# Schematic_-_Ebook_Reader_vFinal_v34.net
KiCad netlist of a schematic drawn in EAGLE
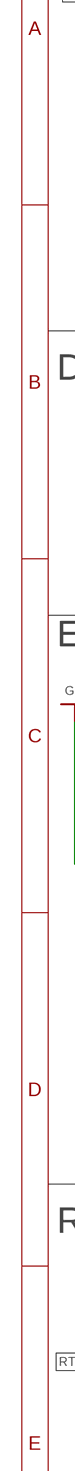
[diagram p0: schematic, sheet 1, part 1 of 2]
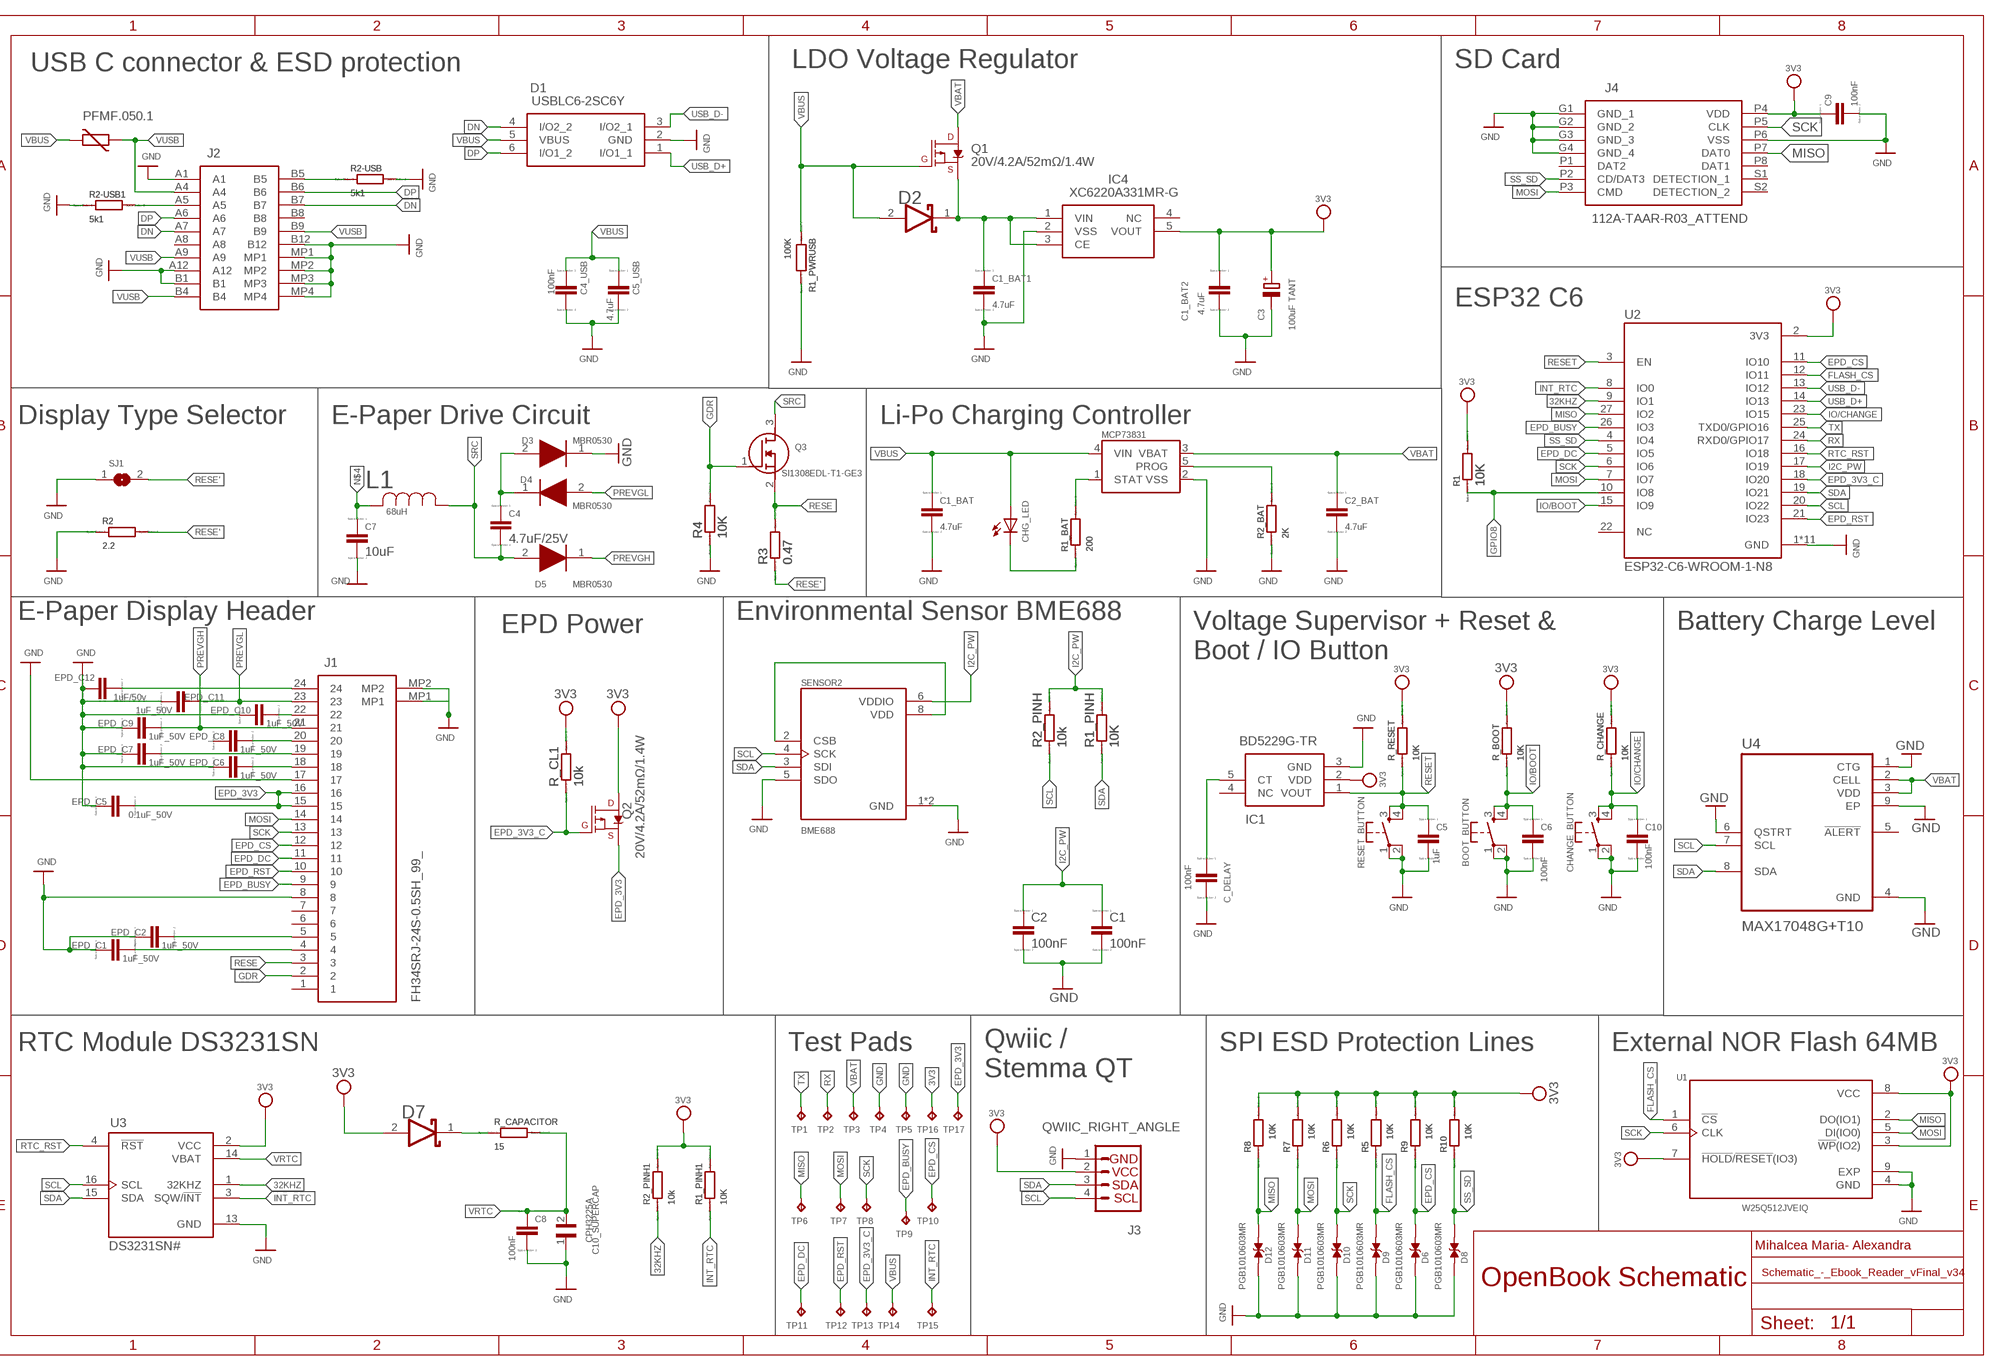
[diagram p1: schematic, sheet 1, part 2 of 2]

(export (version "E")
  (design (tool "Eeschema 10.0.6"))
  (components
    (comp (ref "BOOT_BUTTON")
      (value "BUTTON_CUSYOMV1")
      (footprint "eagle-import:MYBUTTON")
      (libsource (lib "eagle-import") (part "BUTTON_CUSYOMV1"))
    )
    (comp (ref "C1")
      (value "100nF")
      (footprint "eagle-import:EAGLE-LTSPICE_C0402")
      (libsource (lib "eagle-import") (part "EAGLE-LTSPICE_CC0402"))
    )
    (comp (ref "C1_BAT")
      (value "4.7uF")
      (footprint "eagle-import:EAGLE-LTSPICE_C0402")
      (libsource (lib "eagle-import") (part "EAGLE-LTSPICE_CC0402"))
    )
    (comp (ref "C1_BAT1")
      (value "4.7uF")
      (footprint "eagle-import:EAGLE-LTSPICE_C0402")
      (libsource (lib "eagle-import") (part "EAGLE-LTSPICE_CC0402"))
    )
    (comp (ref "C1_BAT2")
      (value "4.7uF")
      (footprint "eagle-import:EAGLE-LTSPICE_C0402")
      (libsource (lib "eagle-import") (part "EAGLE-LTSPICE_CC0402"))
    )
    (comp (ref "C2")
      (value "100nF")
      (footprint "eagle-import:EAGLE-LTSPICE_C0402")
      (libsource (lib "eagle-import") (part "EAGLE-LTSPICE_CC0402"))
    )
    (comp (ref "C2_BAT")
      (value "4.7uF")
      (footprint "eagle-import:EAGLE-LTSPICE_C0402")
      (libsource (lib "eagle-import") (part "EAGLE-LTSPICE_CC0402"))
    )
    (comp (ref "C3")
      (value "100uF TANT")
      (footprint "eagle-import:RCL_CT3528")
      (libsource (lib "eagle-import") (part "RCL_CPOL-EUCT3528"))
    )
    (comp (ref "C4")
      (value "4.7uF/25V")
      (footprint "eagle-import:EAGLE-LTSPICE_C0402")
      (libsource (lib "eagle-import") (part "EAGLE-LTSPICE_CC0402"))
    )
    (comp (ref "C4_USB")
      (value "100nF")
      (footprint "eagle-import:EAGLE-LTSPICE_C0402")
      (libsource (lib "eagle-import") (part "EAGLE-LTSPICE_CC0402"))
    )
    (comp (ref "C5")
      (value "1uF")
      (footprint "eagle-import:EAGLE-LTSPICE_C0402")
      (libsource (lib "eagle-import") (part "EAGLE-LTSPICE_CC0402"))
    )
    (comp (ref "C5_USB")
      (value "4.7uF")
      (footprint "eagle-import:EAGLE-LTSPICE_C0402")
      (libsource (lib "eagle-import") (part "EAGLE-LTSPICE_CC0402"))
    )
    (comp (ref "C6")
      (value "100nF")
      (footprint "eagle-import:EAGLE-LTSPICE_C0402")
      (libsource (lib "eagle-import") (part "EAGLE-LTSPICE_CC0402"))
    )
    (comp (ref "C7")
      (value "10uF")
      (footprint "eagle-import:EAGLE-LTSPICE_C0402")
      (libsource (lib "eagle-import") (part "EAGLE-LTSPICE_CC0402"))
    )
    (comp (ref "C8")
      (value "100nF")
      (footprint "eagle-import:EAGLE-LTSPICE_C0402")
      (libsource (lib "eagle-import") (part "EAGLE-LTSPICE_CC0402"))
    )
    (comp (ref "C9")
      (value "100nF")
      (footprint "eagle-import:EAGLE-LTSPICE_C0402")
      (libsource (lib "eagle-import") (part "EAGLE-LTSPICE_CC0402"))
    )
    (comp (ref "C10")
      (value "100nF")
      (footprint "eagle-import:EAGLE-LTSPICE_C0402")
      (libsource (lib "eagle-import") (part "EAGLE-LTSPICE_CC0402"))
    )
    (comp (ref "C10_SUPERCAP")
      (value "CPH3225A")
      (footprint "eagle-import:CAPCP3225X100N")
      (fields (field (name "MF") "Seiko Instruments"))
      (libsource (lib "eagle-import") (part "CPH3225A"))
    )
    (comp (ref "CHANGE_BUTTON")
      (value "BUTTON_CUSYOMV1")
      (footprint "eagle-import:MYBUTTON")
      (libsource (lib "eagle-import") (part "BUTTON_CUSYOMV1"))
    )
    (comp (ref "CHG_LED")
      (value "ADAFRUIT_LEDCHIP-LED0603")
      (footprint "eagle-import:ADAFRUIT_CHIP-LED0603")
      (libsource (lib "eagle-import") (part "ADAFRUIT_LEDCHIP-LED0603"))
    )
    (comp (ref "C_DELAY")
      (value "100nF")
      (footprint "eagle-import:EAGLE-LTSPICE_C0402")
      (libsource (lib "eagle-import") (part "EAGLE-LTSPICE_CC0402"))
    )
    (comp (ref "D1")
      (value "USBLC6-2SC6Y")
      (footprint "eagle-import:SOT95P280X145-6N")
      (fields (field (name "MF") "STMicroelectronics"))
      (libsource (lib "eagle-import") (part "USBLC6-2SC6Y"))
    )
    (comp (ref "D2")
      (value "ESP32_WROVER_AVX---SD0805S020S1R0_AVX_SD0805S020S1R0_0_0AVX_SD0805S020S1R0_0_0")
      (footprint "eagle-import:ESP32_WROVER_AVX---SD0805S020S1R0_AVX_SD0805S020S1R0_0")
      (fields
        (field (name "DIGIKEY_PART_NUMBER") "478-7800-1-ND")
        (field (name "MF") "AVX")
        (field (name "MOUSER_PART_NUMBER") "581-SD0805S020S1R0")
      )
      (libsource (lib "eagle-import") (part "ESP32_WROVER_AVX---SD0805S020S1R0_AVX_SD0805S020S1R0_0_0AVX_SD0805S020S1R0_0_0"))
    )
    (comp (ref "D3")
      (value "MBR0530")
      (footprint "eagle-import:SOD3716X135N")
      (fields (field (name "MF") "ON Semiconductor"))
      (libsource (lib "eagle-import") (part "MBR0530"))
    )
    (comp (ref "D4")
      (value "MBR0530")
      (footprint "eagle-import:SOD3716X135N")
      (fields (field (name "MF") "ON Semiconductor"))
      (libsource (lib "eagle-import") (part "MBR0530"))
    )
    (comp (ref "D5")
      (value "MBR0530")
      (footprint "eagle-import:SOD3716X135N")
      (fields (field (name "MF") "ON Semiconductor"))
      (libsource (lib "eagle-import") (part "MBR0530"))
    )
    (comp (ref "D6")
      (value "PGB1010603MR")
      (footprint "eagle-import:DIOC1608X36N")
      (fields (field (name "MF") "Littelfuse Inc."))
      (libsource (lib "eagle-import") (part "PGB1010603MR"))
    )
    (comp (ref "D7")
      (value "ESP32_WROVER_AVX---SD0805S020S1R0_AVX_SD0805S020S1R0_0_0AVX_SD0805S020S1R0_0_0")
      (footprint "eagle-import:ESP32_WROVER_AVX---SD0805S020S1R0_AVX_SD0805S020S1R0_0")
      (fields
        (field (name "DIGIKEY_PART_NUMBER") "478-7800-1-ND")
        (field (name "MF") "AVX")
        (field (name "MOUSER_PART_NUMBER") "581-SD0805S020S1R0")
      )
      (libsource (lib "eagle-import") (part "ESP32_WROVER_AVX---SD0805S020S1R0_AVX_SD0805S020S1R0_0_0AVX_SD0805S020S1R0_0_0"))
    )
    (comp (ref "D8")
      (value "PGB1010603MR")
      (footprint "eagle-import:DIOC1608X36N")
      (fields (field (name "MF") "Littelfuse Inc."))
      (libsource (lib "eagle-import") (part "PGB1010603MR"))
    )
    (comp (ref "D9")
      (value "PGB1010603MR")
      (footprint "eagle-import:DIOC1608X36N")
      (fields (field (name "MF") "Littelfuse Inc."))
      (libsource (lib "eagle-import") (part "PGB1010603MR"))
    )
    (comp (ref "D10")
      (value "PGB1010603MR")
      (footprint "eagle-import:DIOC1608X36N")
      (fields (field (name "MF") "Littelfuse Inc."))
      (libsource (lib "eagle-import") (part "PGB1010603MR"))
    )
    (comp (ref "D11")
      (value "PGB1010603MR")
      (footprint "eagle-import:DIOC1608X36N")
      (fields (field (name "MF") "Littelfuse Inc."))
      (libsource (lib "eagle-import") (part "PGB1010603MR"))
    )
    (comp (ref "D12")
      (value "PGB1010603MR")
      (footprint "eagle-import:DIOC1608X36N")
      (fields (field (name "MF") "Littelfuse Inc."))
      (libsource (lib "eagle-import") (part "PGB1010603MR"))
    )
    (comp (ref "EPD_C1")
      (value "1uF_50V")
      (footprint "eagle-import:EAGLE-LTSPICE_C0402")
      (libsource (lib "eagle-import") (part "EAGLE-LTSPICE_CC0402"))
    )
    (comp (ref "EPD_C2")
      (value "1uF_50V")
      (footprint "eagle-import:EAGLE-LTSPICE_C0402")
      (libsource (lib "eagle-import") (part "EAGLE-LTSPICE_CC0402"))
    )
    (comp (ref "EPD_C5")
      (value "0.1uF_50V")
      (footprint "eagle-import:EAGLE-LTSPICE_C0402")
      (libsource (lib "eagle-import") (part "EAGLE-LTSPICE_CC0402"))
    )
    (comp (ref "EPD_C6")
      (value "1uF_50V")
      (footprint "eagle-import:EAGLE-LTSPICE_C0402")
      (libsource (lib "eagle-import") (part "EAGLE-LTSPICE_CC0402"))
    )
    (comp (ref "EPD_C7")
      (value "1uF_50V")
      (footprint "eagle-import:EAGLE-LTSPICE_C0402")
      (libsource (lib "eagle-import") (part "EAGLE-LTSPICE_CC0402"))
    )
    (comp (ref "EPD_C8")
      (value "1uF_50V")
      (footprint "eagle-import:EAGLE-LTSPICE_C0402")
      (libsource (lib "eagle-import") (part "EAGLE-LTSPICE_CC0402"))
    )
    (comp (ref "EPD_C9")
      (value "1uF_50V")
      (footprint "eagle-import:EAGLE-LTSPICE_C0402")
      (libsource (lib "eagle-import") (part "EAGLE-LTSPICE_CC0402"))
    )
    (comp (ref "EPD_C10")
      (value "1uF_50V")
      (footprint "eagle-import:EAGLE-LTSPICE_C0402")
      (libsource (lib "eagle-import") (part "EAGLE-LTSPICE_CC0402"))
    )
    (comp (ref "EPD_C11")
      (value "1uF_50V")
      (footprint "eagle-import:EAGLE-LTSPICE_C0402")
      (libsource (lib "eagle-import") (part "EAGLE-LTSPICE_CC0402"))
    )
    (comp (ref "EPD_C12")
      (value "1uF/50v")
      (footprint "eagle-import:EAGLE-LTSPICE_C0402")
      (libsource (lib "eagle-import") (part "EAGLE-LTSPICE_CC0402"))
    )
    (comp (ref "IC1")
      (value "BD5229G-TR")
      (footprint "eagle-import:SOT95P280X125-5N")
      (fields (field (name "MOUSER_PART_NUMBER") "755-BD5229G-TR"))
      (libsource (lib "eagle-import") (part "BD5229G-TR"))
    )
    (comp (ref "IC4")
      (value "XC6220A331MR-G")
      (footprint "eagle-import:SOT95P280X120-5N")
      (fields (field (name "MOUSER_PART_NUMBER") "865-XC6220A331MR-G"))
      (libsource (lib "eagle-import") (part "XC6220A331MR-G"))
    )
    (comp (ref "J1")
      (value "FH34SRJ-24S-0.5SH_99_")
      (footprint "eagle-import:FH34SRJ24S05SH99")
      (fields
        (field (name "MANUFACTURER_PART_NUMBER") "FH34SRJ-24S-0.5SH(99)")
        (field (name "MOUSER_PART_NUMBER") "798-FH34SRJ24S05SH99")
      )
      (libsource (lib "eagle-import") (part "FH34SRJ-24S-0.5SH_99_"))
    )
    (comp (ref "J2")
      (value "SAMACSYS_PARTS_USB4110-GF-A")
      (footprint "eagle-import:SAMACSYS_PARTS_USB4110GFA")
      (fields
        (field (name "MANUFACTURER_PART_NUMBER") "USB4110-GF-A")
        (field (name "MOUSER_PART_NUMBER") "640-USB4110-GF-A")
      )
      (libsource (lib "eagle-import") (part "SAMACSYS_PARTS_USB4110-GF-A"))
    )
    (comp (ref "J3")
      (value "QWIIC_RIGHT_ANGLE")
      (footprint "eagle-import:JST04_1MM_RA")
      (libsource (lib "eagle-import") (part "QWIIC_CONNECTORJS-1MM"))
    )
    (comp (ref "J4")
      (value "112A-TAAR-R03_ATTEND")
      (footprint "eagle-import:112ATAARR03ATTEND")
      (fields (field (name "MANUFACTURER_PART_NUMBER") "112A-TAAR-R03 ATTEND"))
      (libsource (lib "eagle-import") (part "112A-TAAR-R03_ATTEND"))
    )
    (comp (ref "L1")
      (value "68uH")
      (footprint "eagle-import:IND_4828-WE-TPC_WRE")
      (fields
        (field (name "MANUFACTURER_PART_NUMBER") "744043680")
        (field (name "COPYRIGHT") "Copyright (C) 2024 Ultra Librarian. All rights reserved.")
      )
      (libsource (lib "eagle-import") (part "744043680IND_4828-WE-TPC_WRE"))
    )
    (comp (ref "MCP73831")
      (value "ESP32_WROVER_SPARKFUN-IC-POWER_MCP73831")
      (footprint "eagle-import:ESP32_WROVER_SPARKFUN-IC-POWER_SOT23-5")
      (libsource (lib "eagle-import") (part "ESP32_WROVER_SPARKFUN-IC-POWER_MCP73831"))
    )
    (comp (ref "PFMF.050.1")
      (value "ESP32C6_VARISTORCN1812")
      (footprint "eagle-import:ESP32C6_VARISTOR_CT_CN1812")
      (libsource (lib "eagle-import") (part "ESP32C6_VARISTORCN1812"))
    )
    (comp (ref "Q1")
      (value "20V/4.2A/52mΩ/1.4W")
      (footprint "eagle-import:ESP32_WROVER_SPARKFUN-DISCRETESEMI_SOT23-3")
      (libsource (lib "eagle-import") (part "ESP32_WROVER_SPARKFUN-DISCRETESEMI_MOSFET_PCH-DMG2305UX-7"))
    )
    (comp (ref "Q2")
      (value "20V/4.2A/52mΩ/1.4W")
      (footprint "eagle-import:ESP32_WROVER_SPARKFUN-DISCRETESEMI_SOT23-3")
      (libsource (lib "eagle-import") (part "ESP32_WROVER_SPARKFUN-DISCRETESEMI_MOSFET_PCH-DMG2305UX-7"))
    )
    (comp (ref "Q3")
      (value "SI1308EDL-T1-GE3")
      (footprint "eagle-import:SOT65P210X110-3N")
      (fields (field (name "MF") "Vishay Siliconix"))
      (libsource (lib "eagle-import") (part "SI1308EDL-T1-GE3"))
    )
    (comp (ref "R1")
      (value "10K")
      (footprint "eagle-import:ESP32_WROVER_EAGLE-LTSPICE_R0402")
      (libsource (lib "eagle-import") (part "ESP32_WROVER_EAGLE-LTSPICE_RR0402"))
    )
    (comp (ref "R1_BAT")
      (value "200")
      (footprint "eagle-import:ESP32_WROVER_EAGLE-LTSPICE_R0402")
      (libsource (lib "eagle-import") (part "ESP32_WROVER_EAGLE-LTSPICE_RR0402"))
    )
    (comp (ref "R1_PINH")
      (value "10K")
      (footprint "eagle-import:ESP32_WROVER_EAGLE-LTSPICE_R0402")
      (libsource (lib "eagle-import") (part "ESP32_WROVER_EAGLE-LTSPICE_RR0402"))
    )
    (comp (ref "R1_PINH1")
      (value "10K")
      (footprint "eagle-import:ESP32_WROVER_EAGLE-LTSPICE_R0402")
      (libsource (lib "eagle-import") (part "ESP32_WROVER_EAGLE-LTSPICE_RR0402"))
    )
    (comp (ref "R1_PWRUSB")
      (value "100K")
      (footprint "eagle-import:ESP32_WROVER_EAGLE-LTSPICE_R0402")
      (libsource (lib "eagle-import") (part "ESP32_WROVER_EAGLE-LTSPICE_RR0402"))
    )
    (comp (ref "R2")
      (value "2.2")
      (footprint "eagle-import:ESP32_WROVER_EAGLE-LTSPICE_R0402")
      (libsource (lib "eagle-import") (part "ESP32_WROVER_EAGLE-LTSPICE_RR0402"))
    )
    (comp (ref "R2-USB")
      (value "5k1")
      (footprint "eagle-import:ESP32_WROVER_EAGLE-LTSPICE_R0402")
      (libsource (lib "eagle-import") (part "ESP32_WROVER_EAGLE-LTSPICE_RR0402"))
    )
    (comp (ref "R2-USB1")
      (value "5k1")
      (footprint "eagle-import:ESP32_WROVER_EAGLE-LTSPICE_R0402")
      (libsource (lib "eagle-import") (part "ESP32_WROVER_EAGLE-LTSPICE_RR0402"))
    )
    (comp (ref "R2_BAT")
      (value "2K")
      (footprint "eagle-import:ESP32_WROVER_EAGLE-LTSPICE_R0402")
      (libsource (lib "eagle-import") (part "ESP32_WROVER_EAGLE-LTSPICE_RR0402"))
    )
    (comp (ref "R2_PINH")
      (value "10k")
      (footprint "eagle-import:ESP32_WROVER_EAGLE-LTSPICE_R0402")
      (libsource (lib "eagle-import") (part "ESP32_WROVER_EAGLE-LTSPICE_RR0402"))
    )
    (comp (ref "R2_PINH1")
      (value "10k")
      (footprint "eagle-import:ESP32_WROVER_EAGLE-LTSPICE_R0402")
      (libsource (lib "eagle-import") (part "ESP32_WROVER_EAGLE-LTSPICE_RR0402"))
    )
    (comp (ref "R3")
      (value "0.47")
      (footprint "eagle-import:ESP32_WROVER_EAGLE-LTSPICE_R0402")
      (libsource (lib "eagle-import") (part "ESP32_WROVER_EAGLE-LTSPICE_RR0402"))
    )
    (comp (ref "R4")
      (value "10K")
      (footprint "eagle-import:ESP32_WROVER_EAGLE-LTSPICE_R0402")
      (libsource (lib "eagle-import") (part "ESP32_WROVER_EAGLE-LTSPICE_RR0402"))
    )
    (comp (ref "R5")
      (value "10K")
      (footprint "eagle-import:ESP32_WROVER_EAGLE-LTSPICE_R0402")
      (libsource (lib "eagle-import") (part "ESP32_WROVER_EAGLE-LTSPICE_RR0402"))
    )
    (comp (ref "R6")
      (value "10K")
      (footprint "eagle-import:ESP32_WROVER_EAGLE-LTSPICE_R0402")
      (libsource (lib "eagle-import") (part "ESP32_WROVER_EAGLE-LTSPICE_RR0402"))
    )
    (comp (ref "R7")
      (value "10K")
      (footprint "eagle-import:ESP32_WROVER_EAGLE-LTSPICE_R0402")
      (libsource (lib "eagle-import") (part "ESP32_WROVER_EAGLE-LTSPICE_RR0402"))
    )
    (comp (ref "R8")
      (value "10K")
      (footprint "eagle-import:ESP32_WROVER_EAGLE-LTSPICE_R0402")
      (libsource (lib "eagle-import") (part "ESP32_WROVER_EAGLE-LTSPICE_RR0402"))
    )
    (comp (ref "R9")
      (value "10K")
      (footprint "eagle-import:ESP32_WROVER_EAGLE-LTSPICE_R0402")
      (libsource (lib "eagle-import") (part "ESP32_WROVER_EAGLE-LTSPICE_RR0402"))
    )
    (comp (ref "R10")
      (value "10K")
      (footprint "eagle-import:ESP32_WROVER_EAGLE-LTSPICE_R0402")
      (libsource (lib "eagle-import") (part "ESP32_WROVER_EAGLE-LTSPICE_RR0402"))
    )
    (comp (ref "RESET_BUTTON")
      (value "BUTTON_CUSYOMV1")
      (footprint "eagle-import:MYBUTTON")
      (libsource (lib "eagle-import") (part "BUTTON_CUSYOMV1"))
    )
    (comp (ref "R_BOOT")
      (value "10K")
      (footprint "eagle-import:ESP32_WROVER_EAGLE-LTSPICE_R0402")
      (libsource (lib "eagle-import") (part "ESP32_WROVER_EAGLE-LTSPICE_RR0402"))
    )
    (comp (ref "R_CAPACITOR")
      (value "15")
      (footprint "eagle-import:ESP32_WROVER_EAGLE-LTSPICE_R0402")
      (libsource (lib "eagle-import") (part "ESP32_WROVER_EAGLE-LTSPICE_RR0402"))
    )
    (comp (ref "R_CHANGE")
      (value "10K")
      (footprint "eagle-import:ESP32_WROVER_EAGLE-LTSPICE_R0402")
      (libsource (lib "eagle-import") (part "ESP32_WROVER_EAGLE-LTSPICE_RR0402"))
    )
    (comp (ref "R_CL1")
      (value "10k")
      (footprint "eagle-import:ESP32_WROVER_EAGLE-LTSPICE_R0402")
      (libsource (lib "eagle-import") (part "ESP32_WROVER_EAGLE-LTSPICE_RR0402"))
    )
    (comp (ref "R_RESET")
      (value "10K")
      (footprint "eagle-import:ESP32_WROVER_EAGLE-LTSPICE_R0402")
      (libsource (lib "eagle-import") (part "ESP32_WROVER_EAGLE-LTSPICE_RR0402"))
    )
    (comp (ref "SENSOR2")
      (value "BME688")
      (footprint "eagle-import:ESP32_WROVER_BME680_PSON80P300X300X100-8N")
      (fields (field (name "MF") "Bosch Sensortec") (field (name "MP") "BME680"))
      (libsource (lib "eagle-import") (part "ESP32_WROVER_BME680_BME680"))
    )
    (comp (ref "SJ1") (value "SJ") (footprint "eagle-import:SJ") (libsource (lib "eagle-import") (part "SJ")))
    (comp (ref "TP1")
      (value "TPTP20R")
      (footprint "eagle-import:TP20R")
      (libsource (lib "eagle-import") (part "TPTP20R"))
    )
    (comp (ref "TP2")
      (value "TPTP20R")
      (footprint "eagle-import:TP20R")
      (libsource (lib "eagle-import") (part "TPTP20R"))
    )
    (comp (ref "TP3")
      (value "TPTP20R")
      (footprint "eagle-import:TP20R")
      (libsource (lib "eagle-import") (part "TPTP20R"))
    )
    (comp (ref "TP4")
      (value "TPTP20R")
      (footprint "eagle-import:TP20R")
      (libsource (lib "eagle-import") (part "TPTP20R"))
    )
    (comp (ref "TP5")
      (value "TPTP20R")
      (footprint "eagle-import:TP20R")
      (libsource (lib "eagle-import") (part "TPTP20R"))
    )
    (comp (ref "TP6")
      (value "TPTP20R")
      (footprint "eagle-import:TP20R")
      (libsource (lib "eagle-import") (part "TPTP20R"))
    )
    (comp (ref "TP7")
      (value "TPTP20R")
      (footprint "eagle-import:TP20R")
      (libsource (lib "eagle-import") (part "TPTP20R"))
    )
    (comp (ref "TP8")
      (value "TPTP20R")
      (footprint "eagle-import:TP20R")
      (libsource (lib "eagle-import") (part "TPTP20R"))
    )
    (comp (ref "TP9")
      (value "TPTP20R")
      (footprint "eagle-import:TP20R")
      (libsource (lib "eagle-import") (part "TPTP20R"))
    )
    (comp (ref "TP10")
      (value "TPTP20R")
      (footprint "eagle-import:TP20R")
      (libsource (lib "eagle-import") (part "TPTP20R"))
    )
    (comp (ref "TP11")
      (value "TPTP20R")
      (footprint "eagle-import:TP20R")
      (libsource (lib "eagle-import") (part "TPTP20R"))
    )
    (comp (ref "TP12")
      (value "TPTP20R")
      (footprint "eagle-import:TP20R")
      (libsource (lib "eagle-import") (part "TPTP20R"))
    )
    (comp (ref "TP13")
      (value "TPTP20R")
      (footprint "eagle-import:TP20R")
      (libsource (lib "eagle-import") (part "TPTP20R"))
    )
    (comp (ref "TP14")
      (value "TPTP20R")
      (footprint "eagle-import:TP20R")
      (libsource (lib "eagle-import") (part "TPTP20R"))
    )
    (comp (ref "TP15")
      (value "TPTP20R")
      (footprint "eagle-import:TP20R")
      (libsource (lib "eagle-import") (part "TPTP20R"))
    )
    (comp (ref "TP16")
      (value "TPTP20R")
      (footprint "eagle-import:TP20R")
      (libsource (lib "eagle-import") (part "TPTP20R"))
    )
    (comp (ref "TP17")
      (value "TPTP20R")
      (footprint "eagle-import:TP20R")
      (libsource (lib "eagle-import") (part "TPTP20R"))
    )
    (comp (ref "U1")
      (value "W25Q512JVEIQ")
      (footprint "eagle-import:SON127P600X800X80-9N")
      (fields (field (name "MF") "Winbond Electronics"))
      (libsource (lib "eagle-import") (part "W25Q512JVEIQ"))
    )
    (comp (ref "U2")
      (value "ESP32-C6-WROOM-1-N8")
      (footprint "eagle-import:XCVR_ESP32-C6-WROOM-1-N8")
      (fields (field (name "MF") "Espressif Systems"))
      (libsource (lib "eagle-import") (part "ESP32-C6-WROOM-1-N8"))
    )
    (comp (ref "U3")
      (value "DS3231SN#")
      (footprint "eagle-import:SOIC127P1032X265-16N")
      (fields (field (name "MF") "Analog Devices"))
      (libsource (lib "eagle-import") (part "DS3231SN#"))
    )
    (comp (ref "U4")
      (value "MAX17048G+T10")
      (footprint "eagle-import:SON50P200X200X80-9N")
      (fields (field (name "MF") "Analog Devices"))
      (libsource (lib "eagle-import") (part "MAX17048G+T10"))
    )
  )
  (nets
    (net (code "1") (name "3V3") (class "Default")
      (node (ref "C1_BAT2") (pin "1") (pinfunction "1_1") (pintype "passive"))
      (node (ref "C3") (pin "+") (pinfunction "+_+") (pintype "passive"))
      (node (ref "C9") (pin "1") (pinfunction "1_1") (pintype "passive"))
      (node (ref "D7") (pin "2") (pinfunction "ANODE_2") (pintype "bidirectional"))
      (node (ref "IC1") (pin "2") (pinfunction "VDD_2") (pintype "bidirectional"))
      (node (ref "IC4") (pin "5") (pinfunction "VOUT_5") (pintype "bidirectional"))
      (node (ref "J3") (pin "2") (pinfunction "2_2") (pintype "power_in"))
      (node (ref "J4") (pin "P4") (pinfunction "VDD_P4") (pintype "bidirectional"))
      (node (ref "Q2") (pin "3") (pinfunction "D_3") (pintype "bidirectional"))
      (node (ref "R1") (pin "2") (pinfunction "2_2") (pintype "passive"))
      (node (ref "R10") (pin "2") (pinfunction "2_2") (pintype "passive"))
      (node (ref "R1_PINH1") (pin "2") (pinfunction "2_2") (pintype "passive"))
      (node (ref "R2_PINH1") (pin "2") (pinfunction "2_2") (pintype "passive"))
      (node (ref "R5") (pin "2") (pinfunction "2_2") (pintype "passive"))
      (node (ref "R6") (pin "2") (pinfunction "2_2") (pintype "passive"))
      (node (ref "R7") (pin "2") (pinfunction "2_2") (pintype "passive"))
      (node (ref "R8") (pin "2") (pinfunction "2_2") (pintype "passive"))
      (node (ref "R9") (pin "2") (pinfunction "2_2") (pintype "passive"))
      (node (ref "R_BOOT") (pin "2") (pinfunction "2_2") (pintype "passive"))
      (node (ref "R_CHANGE") (pin "2") (pinfunction "2_2") (pintype "passive"))
      (node (ref "R_CL1") (pin "2") (pinfunction "2_2") (pintype "passive"))
      (node (ref "R_RESET") (pin "2") (pinfunction "2_2") (pintype "passive"))
      (node (ref "TP16") (pin "TP") (pinfunction "TP_TP") (pintype "input"))
      (node (ref "U1") (pin "3") (pinfunction "~{WP}(IO2)_3") (pintype "bidirectional"))
      (node (ref "U1") (pin "7") (pinfunction "~{HOLD}/~{RESET}(IO3)_7") (pintype "bidirectional"))
      (node (ref "U1") (pin "8") (pinfunction "VCC_8") (pintype "power_in"))
      (node (ref "U2") (pin "2") (pinfunction "3V3_2") (pintype "power_in"))
      (node (ref "U3") (pin "2") (pinfunction "VCC_2") (pintype "power_in"))
    )
    (net (code "2") (name "32KHZ") (class "Default")
      (node (ref "R2_PINH1") (pin "1") (pinfunction "1_1") (pintype "passive"))
      (node (ref "U2") (pin "9") (pinfunction "IO1_9") (pintype "bidirectional"))
      (node (ref "U3") (pin "1") (pinfunction "32KHZ_1") (pintype "output"))
    )
    (net (code "3") (name "DN") (class "Default")
      (node (ref "D1") (pin "4") (pinfunction "I/O2_2_4") (pintype "bidirectional"))
      (node (ref "J2") (pin "A7") (pinfunction "A7_A7") (pintype "bidirectional"))
      (node (ref "J2") (pin "B7") (pinfunction "B7_B7") (pintype "bidirectional"))
    )
    (net (code "4") (name "DP") (class "Default")
      (node (ref "D1") (pin "6") (pinfunction "I/O1_2_6") (pintype "bidirectional"))
      (node (ref "J2") (pin "A6") (pinfunction "A6_A6") (pintype "bidirectional"))
      (node (ref "J2") (pin "B6") (pinfunction "B6_B6") (pintype "bidirectional"))
    )
    (net (code "5") (name "EPD_3V3") (class "Default")
      (node (ref "EPD_C5") (pin "2") (pinfunction "2_2") (pintype "passive"))
      (node (ref "J1") (pin "15") (pinfunction "15_15") (pintype "bidirectional"))
      (node (ref "J1") (pin "16") (pinfunction "16_16") (pintype "bidirectional"))
      (node (ref "Q2") (pin "2") (pinfunction "S_2") (pintype "bidirectional"))
      (node (ref "TP17") (pin "TP") (pinfunction "TP_TP") (pintype "input"))
    )
    (net (code "6") (name "EPD_3V3_C") (class "Default")
      (node (ref "Q2") (pin "1") (pinfunction "G_1") (pintype "bidirectional"))
      (node (ref "R_CL1") (pin "1") (pinfunction "1_1") (pintype "passive"))
      (node (ref "TP13") (pin "TP") (pinfunction "TP_TP") (pintype "input"))
      (node (ref "U2") (pin "18") (pinfunction "IO20_18") (pintype "bidirectional"))
    )
    (net (code "7") (name "EPD_BUSY") (class "Default")
      (node (ref "J1") (pin "9") (pinfunction "9_9") (pintype "bidirectional"))
      (node (ref "TP9") (pin "TP") (pinfunction "TP_TP") (pintype "input"))
      (node (ref "U2") (pin "26") (pinfunction "IO3_26") (pintype "bidirectional"))
    )
    (net (code "8") (name "EPD_CS") (class "Default")
      (node (ref "D6") (pin "2") (pinfunction "2_2") (pintype "passive"))
      (node (ref "J1") (pin "12") (pinfunction "12_12") (pintype "bidirectional"))
      (node (ref "R9") (pin "1") (pinfunction "1_1") (pintype "passive"))
      (node (ref "TP10") (pin "TP") (pinfunction "TP_TP") (pintype "input"))
      (node (ref "U2") (pin "11") (pinfunction "IO10_11") (pintype "bidirectional"))
    )
    (net (code "9") (name "EPD_DC") (class "Default")
      (node (ref "J1") (pin "11") (pinfunction "11_11") (pintype "bidirectional"))
      (node (ref "TP11") (pin "TP") (pinfunction "TP_TP") (pintype "input"))
      (node (ref "U2") (pin "5") (pinfunction "IO5_5") (pintype "bidirectional"))
    )
    (net (code "10") (name "EPD_RST") (class "Default")
      (node (ref "J1") (pin "10") (pinfunction "10_10") (pintype "bidirectional"))
      (node (ref "TP12") (pin "TP") (pinfunction "TP_TP") (pintype "input"))
      (node (ref "U2") (pin "21") (pinfunction "IO23_21") (pintype "bidirectional"))
    )
    (net (code "11") (name "FLASH_CS") (class "Default")
      (node (ref "D9") (pin "2") (pinfunction "2_2") (pintype "passive"))
      (node (ref "R5") (pin "1") (pinfunction "1_1") (pintype "passive"))
      (node (ref "U1") (pin "1") (pinfunction "~{CS}_1") (pintype "input"))
      (node (ref "U2") (pin "12") (pinfunction "IO11_12") (pintype "bidirectional"))
    )
    (net (code "12") (name "GDR") (class "Default")
      (node (ref "J1") (pin "2") (pinfunction "2_2") (pintype "bidirectional"))
      (node (ref "Q3") (pin "1") (pinfunction "G_1") (pintype "bidirectional"))
      (node (ref "R4") (pin "2") (pinfunction "2_2") (pintype "passive"))
    )
    (net (code "13") (name "GND") (class "Default")
      (node (ref "BOOT_BUTTON") (pin "1") (pinfunction "1_1") (pintype "passive"))
      (node (ref "BOOT_BUTTON") (pin "2") (pinfunction "2_2") (pintype "passive"))
      (node (ref "C1") (pin "2") (pinfunction "2_2") (pintype "passive"))
      (node (ref "C10") (pin "2") (pinfunction "2_2") (pintype "passive"))
      (node (ref "C10_SUPERCAP") (pin "1") (pinfunction "1_1") (pintype "passive"))
      (node (ref "C1_BAT") (pin "2") (pinfunction "2_2") (pintype "passive"))
      (node (ref "C1_BAT1") (pin "2") (pinfunction "2_2") (pintype "passive"))
      (node (ref "C1_BAT2") (pin "2") (pinfunction "2_2") (pintype "passive"))
      (node (ref "C2") (pin "2") (pinfunction "2_2") (pintype "passive"))
      (node (ref "C2_BAT") (pin "2") (pinfunction "2_2") (pintype "passive"))
      (node (ref "C3") (pin "-") (pinfunction "-_-") (pintype "passive"))
      (node (ref "C4_USB") (pin "2") (pinfunction "2_2") (pintype "passive"))
      (node (ref "C5") (pin "2") (pinfunction "2_2") (pintype "passive"))
      (node (ref "C5_USB") (pin "2") (pinfunction "2_2") (pintype "passive"))
      (node (ref "C6") (pin "2") (pinfunction "2_2") (pintype "passive"))
      (node (ref "C7") (pin "2") (pinfunction "2_2") (pintype "passive"))
      (node (ref "C8") (pin "2") (pinfunction "2_2") (pintype "passive"))
      (node (ref "C9") (pin "2") (pinfunction "2_2") (pintype "passive"))
      (node (ref "CHANGE_BUTTON") (pin "1") (pinfunction "1_1") (pintype "passive"))
      (node (ref "CHANGE_BUTTON") (pin "2") (pinfunction "2_2") (pintype "passive"))
      (node (ref "C_DELAY") (pin "2") (pinfunction "2_2") (pintype "passive"))
      (node (ref "D1") (pin "2") (pinfunction "GND_2") (pintype "bidirectional"))
      (node (ref "D10") (pin "1") (pinfunction "1_1") (pintype "passive"))
      (node (ref "D11") (pin "1") (pinfunction "1_1") (pintype "passive"))
      (node (ref "D12") (pin "1") (pinfunction "1_1") (pintype "passive"))
      (node (ref "D3") (pin "1") (pinfunction "K_1") (pintype "bidirectional"))
      (node (ref "D6") (pin "1") (pinfunction "1_1") (pintype "passive"))
      (node (ref "D8") (pin "1") (pinfunction "1_1") (pintype "passive"))
      (node (ref "D9") (pin "1") (pinfunction "1_1") (pintype "passive"))
      (node (ref "EPD_C1") (pin "1") (pinfunction "1_1") (pintype "passive"))
      (node (ref "EPD_C10") (pin "1") (pinfunction "1_1") (pintype "passive"))
      (node (ref "EPD_C11") (pin "1") (pinfunction "1_1") (pintype "passive"))
      (node (ref "EPD_C12") (pin "1") (pinfunction "1_1") (pintype "passive"))
      (node (ref "EPD_C2") (pin "1") (pinfunction "1_1") (pintype "passive"))
      (node (ref "EPD_C5") (pin "1") (pinfunction "1_1") (pintype "passive"))
      (node (ref "EPD_C6") (pin "1") (pinfunction "1_1") (pintype "passive"))
      (node (ref "EPD_C7") (pin "1") (pinfunction "1_1") (pintype "passive"))
      (node (ref "EPD_C9") (pin "1") (pinfunction "1_1") (pintype "passive"))
      (node (ref "IC1") (pin "3") (pinfunction "GND_3") (pintype "bidirectional"))
      (node (ref "IC4") (pin "2") (pinfunction "VSS_2") (pintype "bidirectional"))
      (node (ref "J1") (pin "17") (pinfunction "17_17") (pintype "bidirectional"))
      (node (ref "J1") (pin "8") (pinfunction "8_8") (pintype "bidirectional"))
      (node (ref "J1") (pin "MP1") (pinfunction "MP1_MP1") (pintype "bidirectional"))
      (node (ref "J1") (pin "MP2") (pinfunction "MP2_MP2") (pintype "bidirectional"))
      (node (ref "J2") (pin "A1") (pinfunction "A1_A1") (pintype "bidirectional"))
      (node (ref "J2") (pin "A12") (pinfunction "A12_A12") (pintype "bidirectional"))
      (node (ref "J2") (pin "B1") (pinfunction "B1_B1") (pintype "bidirectional"))
      (node (ref "J2") (pin "B12") (pinfunction "B12_B12") (pintype "bidirectional"))
      (node (ref "J2") (pin "MP1") (pinfunction "MP1_MP1") (pintype "bidirectional"))
      (node (ref "J2") (pin "MP2") (pinfunction "MP2_MP2") (pintype "bidirectional"))
      (node (ref "J2") (pin "MP3") (pinfunction "MP3_MP3") (pintype "bidirectional"))
      (node (ref "J2") (pin "MP4") (pinfunction "MP4_MP4") (pintype "bidirectional"))
      (node (ref "J3") (pin "1") (pinfunction "1_1") (pintype "power_in"))
      (node (ref "J4") (pin "G1") (pinfunction "GND_1_G1") (pintype "bidirectional"))
      (node (ref "J4") (pin "G2") (pinfunction "GND_2_G2") (pintype "bidirectional"))
      (node (ref "J4") (pin "G3") (pinfunction "GND_3_G3") (pintype "bidirectional"))
      (node (ref "J4") (pin "G4") (pinfunction "GND_4_G4") (pintype "bidirectional"))
      (node (ref "J4") (pin "P6") (pinfunction "VSS_P6") (pintype "bidirectional"))
      (node (ref "MCP73831") (pin "2") (pinfunction "VSS_2") (pintype "power_in"))
      (node (ref "R1_PWRUSB") (pin "2") (pinfunction "2_2") (pintype "passive"))
      (node (ref "R2") (pin "1") (pinfunction "1_1") (pintype "passive"))
      (node (ref "R2-USB") (pin "2") (pinfunction "2_2") (pintype "passive"))
      (node (ref "R2-USB1") (pin "1") (pinfunction "1_1") (pintype "passive"))
      (node (ref "R2_BAT") (pin "1") (pinfunction "1_1") (pintype "passive"))
      (node (ref "R4") (pin "1") (pinfunction "1_1") (pintype "passive"))
      (node (ref "RESET_BUTTON") (pin "1") (pinfunction "1_1") (pintype "passive"))
      (node (ref "RESET_BUTTON") (pin "2") (pinfunction "2_2") (pintype "passive"))
      (node (ref "SENSOR2") (pin "1") (pinfunction "GND_1") (pintype "power_in"))
      (node (ref "SENSOR2") (pin "5") (pinfunction "SDO_5") (pintype "bidirectional"))
      (node (ref "SENSOR2") (pin "7") (pinfunction "GND_7") (pintype "power_in"))
      (node (ref "SJ1") (pin "1") (pinfunction "1_1") (pintype "passive"))
      (node (ref "TP4") (pin "TP") (pinfunction "TP_TP") (pintype "input"))
      (node (ref "TP5") (pin "TP") (pinfunction "TP_TP") (pintype "input"))
      (node (ref "U1") (pin "4") (pinfunction "GND_4") (pintype "power_in"))
      (node (ref "U1") (pin "9") (pinfunction "EXP_9") (pintype "passive"))
      (node (ref "U2") (pin "1") (pinfunction "GND_1") (pintype "power_in"))
      (node (ref "U2") (pin "28") (pinfunction "GND_28") (pintype "power_in"))
      (node (ref "U2") (pin "29_1") (pinfunction "GND_29_1") (pintype "power_in"))
      (node (ref "U2") (pin "29_2") (pinfunction "GND_29_2") (pintype "power_in"))
      (node (ref "U2") (pin "29_3") (pinfunction "GND_29_3") (pintype "power_in"))
      (node (ref "U2") (pin "29_4") (pinfunction "GND_29_4") (pintype "power_in"))
      (node (ref "U2") (pin "29_5") (pinfunction "GND_29_5") (pintype "power_in"))
      (node (ref "U2") (pin "29_6") (pinfunction "GND_29_6") (pintype "power_in"))
      (node (ref "U2") (pin "29_7") (pinfunction "GND_29_7") (pintype "power_in"))
      (node (ref "U2") (pin "29_8") (pinfunction "GND_29_8") (pintype "power_in"))
      (node (ref "U2") (pin "29_9") (pinfunction "GND_29_9") (pintype "power_in"))
      (node (ref "U3") (pin "13") (pinfunction "GND_13") (pintype "power_in"))
      (node (ref "U4") (pin "1") (pinfunction "CTG_1") (pintype "power_in"))
      (node (ref "U4") (pin "4") (pinfunction "GND_4") (pintype "power_in"))
      (node (ref "U4") (pin "6") (pinfunction "QSTRT_6") (pintype "input"))
      (node (ref "U4") (pin "9") (pinfunction "EP_9") (pintype "power_in"))
    )
    (net (code "14") (name "GPIO8") (class "Default")
      (node (ref "R1") (pin "1") (pinfunction "1_1") (pintype "passive"))
      (node (ref "U2") (pin "10") (pinfunction "IO8_10") (pintype "bidirectional"))
    )
    (net (code "15") (name "I2C_PW") (class "Default")
      (node (ref "C1") (pin "1") (pinfunction "1_1") (pintype "passive"))
      (node (ref "C2") (pin "1") (pinfunction "1_1") (pintype "passive"))
      (node (ref "R1_PINH") (pin "2") (pinfunction "2_2") (pintype "passive"))
      (node (ref "R2_PINH") (pin "2") (pinfunction "2_2") (pintype "passive"))
      (node (ref "SENSOR2") (pin "6") (pinfunction "VDDIO_6") (pintype "power_in"))
      (node (ref "U2") (pin "17") (pinfunction "IO19_17") (pintype "bidirectional"))
    )
    (net (code "16") (name "INT_RTC") (class "Default")
      (node (ref "R1_PINH1") (pin "1") (pinfunction "1_1") (pintype "passive"))
      (node (ref "TP15") (pin "TP") (pinfunction "TP_TP") (pintype "input"))
      (node (ref "U2") (pin "8") (pinfunction "IO0_8") (pintype "bidirectional"))
      (node (ref "U3") (pin "3") (pinfunction "SQW/~{INT}_3") (pintype "output"))
    )
    (net (code "17") (name "IO{slash}BOOT") (class "Default")
      (node (ref "BOOT_BUTTON") (pin "3") (pinfunction "3_3") (pintype "passive"))
      (node (ref "BOOT_BUTTON") (pin "4") (pinfunction "4_4") (pintype "passive"))
      (node (ref "C6") (pin "1") (pinfunction "1_1") (pintype "passive"))
      (node (ref "R_BOOT") (pin "1") (pinfunction "1_1") (pintype "passive"))
      (node (ref "U2") (pin "15") (pinfunction "IO9_15") (pintype "bidirectional"))
    )
    (net (code "18") (name "IO{slash}CHANGE") (class "Default")
      (node (ref "C10") (pin "1") (pinfunction "1_1") (pintype "passive"))
      (node (ref "CHANGE_BUTTON") (pin "3") (pinfunction "3_3") (pintype "passive"))
      (node (ref "CHANGE_BUTTON") (pin "4") (pinfunction "4_4") (pintype "passive"))
      (node (ref "R_CHANGE") (pin "1") (pinfunction "1_1") (pintype "passive"))
      (node (ref "U2") (pin "23") (pinfunction "IO15_23") (pintype "bidirectional"))
    )
    (net (code "19") (name "MISO") (class "Default")
      (node (ref "D12") (pin "2") (pinfunction "2_2") (pintype "passive"))
      (node (ref "J4") (pin "P7") (pinfunction "DAT0_P7") (pintype "bidirectional"))
      (node (ref "R8") (pin "1") (pinfunction "1_1") (pintype "passive"))
      (node (ref "TP6") (pin "TP") (pinfunction "TP_TP") (pintype "input"))
      (node (ref "U1") (pin "2") (pinfunction "DO(IO1)_2") (pintype "bidirectional"))
      (node (ref "U2") (pin "27") (pinfunction "IO2_27") (pintype "bidirectional"))
    )
    (net (code "20") (name "MOSI") (class "Default")
      (node (ref "D11") (pin "2") (pinfunction "2_2") (pintype "passive"))
      (node (ref "J1") (pin "14") (pinfunction "14_14") (pintype "bidirectional"))
      (node (ref "J4") (pin "P3") (pinfunction "CMD_P3") (pintype "bidirectional"))
      (node (ref "R7") (pin "1") (pinfunction "1_1") (pintype "passive"))
      (node (ref "TP7") (pin "TP") (pinfunction "TP_TP") (pintype "input"))
      (node (ref "U1") (pin "5") (pinfunction "DI(IO0)_5") (pintype "bidirectional"))
      (node (ref "U2") (pin "7") (pinfunction "IO7_7") (pintype "bidirectional"))
    )
    (net (code "21") (name "N$4") (class "Default")
      (node (ref "C7") (pin "1") (pinfunction "1_1") (pintype "passive"))
      (node (ref "L1") (pin "2") (pinfunction "2_2") (pintype "passive"))
    )
    (net (code "22") (name "Net-(CHG_LED-PadC)") (class "Default")
      (node (ref "CHG_LED") (pin "C") (pinfunction "C_C") (pintype "passive"))
      (node (ref "R1_BAT") (pin "1") (pinfunction "1_1") (pintype "passive"))
    )
    (net (code "23") (name "Net-(D2-CATHODE)") (class "Default")
      (node (ref "C1_BAT1") (pin "1") (pinfunction "1_1") (pintype "passive"))
      (node (ref "D2") (pin "1") (pinfunction "CATHODE_1") (pintype "bidirectional"))
      (node (ref "IC4") (pin "1") (pinfunction "VIN_1") (pintype "bidirectional"))
      (node (ref "IC4") (pin "3") (pinfunction "CE_3") (pintype "bidirectional"))
      (node (ref "Q1") (pin "2") (pinfunction "S_2") (pintype "bidirectional"))
    )
    (net (code "24") (name "Net-(D3-A)") (class "Default")
      (node (ref "C4") (pin "1") (pinfunction "1_1") (pintype "passive"))
      (node (ref "D3") (pin "2") (pinfunction "A_2") (pintype "bidirectional"))
      (node (ref "D4") (pin "1") (pinfunction "K_1") (pintype "bidirectional"))
    )
    (net (code "25") (name "Net-(D7-CATHODE)") (class "Default")
      (node (ref "D7") (pin "1") (pinfunction "CATHODE_1") (pintype "bidirectional"))
      (node (ref "R_CAPACITOR") (pin "1") (pinfunction "1_1") (pintype "passive"))
    )
    (net (code "26") (name "Net-(EPD_C1-Pad2)") (class "Default")
      (node (ref "EPD_C1") (pin "2") (pinfunction "2_2") (pintype "passive"))
      (node (ref "J1") (pin "4") (pinfunction "4_4") (pintype "bidirectional"))
    )
    (net (code "27") (name "Net-(EPD_C2-Pad2)") (class "Default")
      (node (ref "EPD_C2") (pin "2") (pinfunction "2_2") (pintype "passive"))
      (node (ref "J1") (pin "5") (pinfunction "5_5") (pintype "bidirectional"))
    )
    (net (code "28") (name "Net-(EPD_C6-Pad2)") (class "Default")
      (node (ref "EPD_C6") (pin "2") (pinfunction "2_2") (pintype "passive"))
      (node (ref "J1") (pin "18") (pinfunction "18_18") (pintype "bidirectional"))
    )
    (net (code "29") (name "Net-(EPD_C7-Pad2)") (class "Default")
      (node (ref "EPD_C7") (pin "2") (pinfunction "2_2") (pintype "passive"))
      (node (ref "J1") (pin "19") (pinfunction "19_19") (pintype "bidirectional"))
    )
    (net (code "30") (name "Net-(EPD_C8-Pad2)") (class "Default")
      (node (ref "EPD_C8") (pin "2") (pinfunction "2_2") (pintype "passive"))
      (node (ref "J1") (pin "20") (pinfunction "20_20") (pintype "bidirectional"))
    )
    (net (code "31") (name "Net-(EPD_C10-Pad2)") (class "Default")
      (node (ref "EPD_C10") (pin "2") (pinfunction "2_2") (pintype "passive"))
      (node (ref "J1") (pin "22") (pinfunction "22_22") (pintype "bidirectional"))
    )
    (net (code "32") (name "Net-(EPD_C12-Pad2)") (class "Default")
      (node (ref "EPD_C12") (pin "2") (pinfunction "2_2") (pintype "passive"))
      (node (ref "J1") (pin "24") (pinfunction "24_24") (pintype "bidirectional"))
    )
    (net (code "33") (name "Net-(IC1-CT)") (class "Default")
      (node (ref "C_DELAY") (pin "1") (pinfunction "1_1") (pintype "passive"))
      (node (ref "IC1") (pin "5") (pinfunction "CT_5") (pintype "bidirectional"))
    )
    (net (code "34") (name "Net-(J2-PadA5)") (class "Default")
      (node (ref "J2") (pin "A5") (pinfunction "A5_A5") (pintype "bidirectional"))
      (node (ref "R2-USB1") (pin "2") (pinfunction "2_2") (pintype "passive"))
    )
    (net (code "35") (name "Net-(J2-PadB5)") (class "Default")
      (node (ref "J2") (pin "B5") (pinfunction "B5_B5") (pintype "bidirectional"))
      (node (ref "R2-USB") (pin "1") (pinfunction "1_1") (pintype "passive"))
    )
    (net (code "36") (name "Net-(MCP73831-PROG)") (class "Default")
      (node (ref "MCP73831") (pin "5") (pinfunction "PROG_5") (pintype "input"))
      (node (ref "R2_BAT") (pin "2") (pinfunction "2_2") (pintype "passive"))
    )
    (net (code "37") (name "Net-(MCP73831-STAT)") (class "Default")
      (node (ref "MCP73831") (pin "1") (pinfunction "STAT_1") (pintype "output"))
      (node (ref "R1_BAT") (pin "2") (pinfunction "2_2") (pintype "passive"))
    )
    (net (code "38") (name "Net-(SENSOR2-CSB)") (class "Default")
      (node (ref "SENSOR2") (pin "2") (pinfunction "CSB_2") (pintype "input"))
      (node (ref "SENSOR2") (pin "8") (pinfunction "VDD_8") (pintype "power_in"))
    )
    (net (code "39") (name "PREVGH") (class "Default")
      (node (ref "D5") (pin "1") (pinfunction "K_1") (pintype "bidirectional"))
      (node (ref "EPD_C9") (pin "2") (pinfunction "2_2") (pintype "passive"))
      (node (ref "J1") (pin "21") (pinfunction "21_21") (pintype "bidirectional"))
    )
    (net (code "40") (name "PREVGL") (class "Default")
      (node (ref "D4") (pin "2") (pinfunction "A_2") (pintype "bidirectional"))
      (node (ref "EPD_C11") (pin "2") (pinfunction "2_2") (pintype "passive"))
      (node (ref "J1") (pin "23") (pinfunction "23_23") (pintype "bidirectional"))
    )
    (net (code "41") (name "RESE") (class "Default")
      (node (ref "J1") (pin "3") (pinfunction "3_3") (pintype "bidirectional"))
      (node (ref "Q3") (pin "2") (pinfunction "S_2") (pintype "bidirectional"))
      (node (ref "R3") (pin "2") (pinfunction "2_2") (pintype "passive"))
    )
    (net (code "42") (name "RESE'") (class "Default")
      (node (ref "R2") (pin "2") (pinfunction "2_2") (pintype "passive"))
      (node (ref "R3") (pin "1") (pinfunction "1_1") (pintype "passive"))
      (node (ref "SJ1") (pin "2") (pinfunction "2_2") (pintype "passive"))
    )
    (net (code "43") (name "RESET") (class "Default")
      (node (ref "C5") (pin "1") (pinfunction "1_1") (pintype "passive"))
      (node (ref "IC1") (pin "1") (pinfunction "VOUT_1") (pintype "bidirectional"))
      (node (ref "RESET_BUTTON") (pin "3") (pinfunction "3_3") (pintype "passive"))
      (node (ref "RESET_BUTTON") (pin "4") (pinfunction "4_4") (pintype "passive"))
      (node (ref "R_RESET") (pin "1") (pinfunction "1_1") (pintype "passive"))
      (node (ref "U2") (pin "3") (pinfunction "EN_3") (pintype "input"))
    )
    (net (code "44") (name "RTC_RST") (class "Default")
      (node (ref "U2") (pin "16") (pinfunction "IO18_16") (pintype "bidirectional"))
      (node (ref "U3") (pin "4") (pinfunction "~{RST}_4") (pintype "input"))
    )
    (net (code "45") (name "RX") (class "Default")
      (node (ref "TP2") (pin "TP") (pinfunction "TP_TP") (pintype "input"))
      (node (ref "U2") (pin "24") (pinfunction "RXD0/GPIO17_24") (pintype "bidirectional"))
    )
    (net (code "46") (name "SCK") (class "Default")
      (node (ref "D10") (pin "2") (pinfunction "2_2") (pintype "passive"))
      (node (ref "J1") (pin "13") (pinfunction "13_13") (pintype "bidirectional"))
      (node (ref "J4") (pin "P5") (pinfunction "CLK_P5") (pintype "bidirectional"))
      (node (ref "R6") (pin "1") (pinfunction "1_1") (pintype "passive"))
      (node (ref "TP8") (pin "TP") (pinfunction "TP_TP") (pintype "input"))
      (node (ref "U1") (pin "6") (pinfunction "CLK_6") (pintype "input"))
      (node (ref "U2") (pin "6") (pinfunction "IO6_6") (pintype "bidirectional"))
    )
    (net (code "47") (name "SCL") (class "Default")
      (node (ref "J3") (pin "4") (pinfunction "4_4") (pintype "passive"))
      (node (ref "R2_PINH") (pin "1") (pinfunction "1_1") (pintype "passive"))
      (node (ref "SENSOR2") (pin "4") (pinfunction "SCK_4") (pintype "input"))
      (node (ref "U2") (pin "20") (pinfunction "IO22_20") (pintype "bidirectional"))
      (node (ref "U3") (pin "16") (pinfunction "SCL_16") (pintype "input"))
      (node (ref "U4") (pin "7") (pinfunction "SCL_7") (pintype "input"))
    )
    (net (code "48") (name "SDA") (class "Default")
      (node (ref "J3") (pin "3") (pinfunction "3_3") (pintype "passive"))
      (node (ref "R1_PINH") (pin "1") (pinfunction "1_1") (pintype "passive"))
      (node (ref "SENSOR2") (pin "3") (pinfunction "SDI_3") (pintype "bidirectional"))
      (node (ref "U2") (pin "19") (pinfunction "IO21_19") (pintype "bidirectional"))
      (node (ref "U3") (pin "15") (pinfunction "SDA_15") (pintype "bidirectional"))
      (node (ref "U4") (pin "8") (pinfunction "SDA_8") (pintype "bidirectional"))
    )
    (net (code "49") (name "SRC") (class "Default")
      (node (ref "C4") (pin "2") (pinfunction "2_2") (pintype "passive"))
      (node (ref "D5") (pin "2") (pinfunction "A_2") (pintype "bidirectional"))
      (node (ref "L1") (pin "1") (pinfunction "1_1") (pintype "passive"))
      (node (ref "Q3") (pin "3") (pinfunction "D_3") (pintype "bidirectional"))
    )
    (net (code "50") (name "SS_SD") (class "Default")
      (node (ref "D8") (pin "2") (pinfunction "2_2") (pintype "passive"))
      (node (ref "J4") (pin "P2") (pinfunction "CD/DAT3_P2") (pintype "bidirectional"))
      (node (ref "R10") (pin "1") (pinfunction "1_1") (pintype "passive"))
      (node (ref "U2") (pin "4") (pinfunction "IO4_4") (pintype "bidirectional"))
    )
    (net (code "51") (name "TX") (class "Default")
      (node (ref "TP1") (pin "TP") (pinfunction "TP_TP") (pintype "input"))
      (node (ref "U2") (pin "25") (pinfunction "TXD0/GPIO16_25") (pintype "bidirectional"))
    )
    (net (code "52") (name "USB_D+") (class "Default")
      (node (ref "D1") (pin "1") (pinfunction "I/O1_1_1") (pintype "bidirectional"))
      (node (ref "U2") (pin "14") (pinfunction "IO13_14") (pintype "bidirectional"))
    )
    (net (code "53") (name "USB_D-") (class "Default")
      (node (ref "D1") (pin "3") (pinfunction "I/O2_1_3") (pintype "bidirectional"))
      (node (ref "U2") (pin "13") (pinfunction "IO12_13") (pintype "bidirectional"))
    )
    (net (code "54") (name "VBAT") (class "Default")
      (node (ref "C2_BAT") (pin "1") (pinfunction "1_1") (pintype "passive"))
      (node (ref "MCP73831") (pin "3") (pinfunction "VBAT_3") (pintype "power_in"))
      (node (ref "Q1") (pin "3") (pinfunction "D_3") (pintype "bidirectional"))
      (node (ref "TP3") (pin "TP") (pinfunction "TP_TP") (pintype "input"))
      (node (ref "U4") (pin "2") (pinfunction "CELL_2") (pintype "power_in"))
      (node (ref "U4") (pin "3") (pinfunction "VDD_3") (pintype "power_in"))
    )
    (net (code "55") (name "VBUS") (class "Default")
      (node (ref "C1_BAT") (pin "1") (pinfunction "1_1") (pintype "passive"))
      (node (ref "C4_USB") (pin "1") (pinfunction "1_1") (pintype "passive"))
      (node (ref "C5_USB") (pin "1") (pinfunction "1_1") (pintype "passive"))
      (node (ref "CHG_LED") (pin "A") (pinfunction "A_A") (pintype "passive"))
      (node (ref "D1") (pin "5") (pinfunction "VBUS_5") (pintype "bidirectional"))
      (node (ref "D2") (pin "2") (pinfunction "ANODE_2") (pintype "bidirectional"))
      (node (ref "MCP73831") (pin "4") (pinfunction "VIN_4") (pintype "power_in"))
      (node (ref "PFMF.050.1") (pin "2") (pinfunction "2_2") (pintype "passive"))
      (node (ref "Q1") (pin "1") (pinfunction "G_1") (pintype "bidirectional"))
      (node (ref "R1_PWRUSB") (pin "1") (pinfunction "1_1") (pintype "passive"))
      (node (ref "TP14") (pin "TP") (pinfunction "TP_TP") (pintype "input"))
    )
    (net (code "56") (name "VRTC") (class "Default")
      (node (ref "C10_SUPERCAP") (pin "2") (pinfunction "2_2") (pintype "passive"))
      (node (ref "C8") (pin "1") (pinfunction "1_1") (pintype "passive"))
      (node (ref "R_CAPACITOR") (pin "2") (pinfunction "2_2") (pintype "passive"))
      (node (ref "U3") (pin "14") (pinfunction "VBAT_14") (pintype "power_in"))
    )
    (net (code "57") (name "VUSB") (class "Default")
      (node (ref "J2") (pin "A4") (pinfunction "A4_A4") (pintype "bidirectional"))
      (node (ref "J2") (pin "A9") (pinfunction "A9_A9") (pintype "bidirectional"))
      (node (ref "J2") (pin "B4") (pinfunction "B4_B4") (pintype "bidirectional"))
      (node (ref "J2") (pin "B9") (pinfunction "B9_B9") (pintype "bidirectional"))
      (node (ref "PFMF.050.1") (pin "1") (pinfunction "1_1") (pintype "passive"))
    )
    (net (code "58") (name "unconnected-(EPD_C8-Pad1)") (class "Default")
      (node (ref "EPD_C8") (pin "1") (pinfunction "1_1") (pintype "passive"))
    )
    (net (code "59") (name "unconnected-(IC1-NC-Pad4)") (class "Default")
      (node (ref "IC1") (pin "4") (pinfunction "NC_4") (pintype "no_connect"))
    )
    (net (code "60") (name "unconnected-(IC4-NC-Pad4)") (class "Default")
      (node (ref "IC4") (pin "4") (pinfunction "NC_4") (pintype "no_connect"))
    )
    (net (code "61") (name "unconnected-(J1-Pad1)") (class "Default")
      (node (ref "J1") (pin "1") (pinfunction "1_1") (pintype "bidirectional"))
    )
    (net (code "62") (name "unconnected-(J1-Pad6)") (class "Default")
      (node (ref "J1") (pin "6") (pinfunction "6_6") (pintype "bidirectional"))
    )
    (net (code "63") (name "unconnected-(J1-Pad7)") (class "Default")
      (node (ref "J1") (pin "7") (pinfunction "7_7") (pintype "bidirectional"))
    )
    (net (code "64") (name "unconnected-(J2-PadA8)") (class "Default")
      (node (ref "J2") (pin "A8") (pinfunction "A8_A8") (pintype "bidirectional"))
    )
    (net (code "65") (name "unconnected-(J2-PadB8)") (class "Default")
      (node (ref "J2") (pin "B8") (pinfunction "B8_B8") (pintype "bidirectional"))
    )
    (net (code "66") (name "unconnected-(J4-DAT1-PadP8)") (class "Default")
      (node (ref "J4") (pin "P8") (pinfunction "DAT1_P8") (pintype "bidirectional"))
    )
    (net (code "67") (name "unconnected-(J4-DAT2-PadP1)") (class "Default")
      (node (ref "J4") (pin "P1") (pinfunction "DAT2_P1") (pintype "bidirectional"))
    )
    (net (code "68") (name "unconnected-(J4-DETECTION_1-PadS1)") (class "Default")
      (node (ref "J4") (pin "S1") (pinfunction "DETECTION_1_S1") (pintype "bidirectional"))
    )
    (net (code "69") (name "unconnected-(J4-DETECTION_2-PadS2)") (class "Default")
      (node (ref "J4") (pin "S2") (pinfunction "DETECTION_2_S2") (pintype "bidirectional"))
    )
    (net (code "70") (name "unconnected-(U2-NC-Pad22)") (class "Default")
      (node (ref "U2") (pin "22") (pinfunction "NC_22") (pintype "no_connect"))
    )
    (net (code "71") (name "unconnected-(U4-~{ALERT}-Pad5)") (class "Default")
      (node (ref "U4") (pin "5") (pinfunction "~{ALERT}_5") (pintype "output"))
    )
  )
)
